# IR_Transceiver.net
KiCad netlist of a schematic drawn in EAGLE
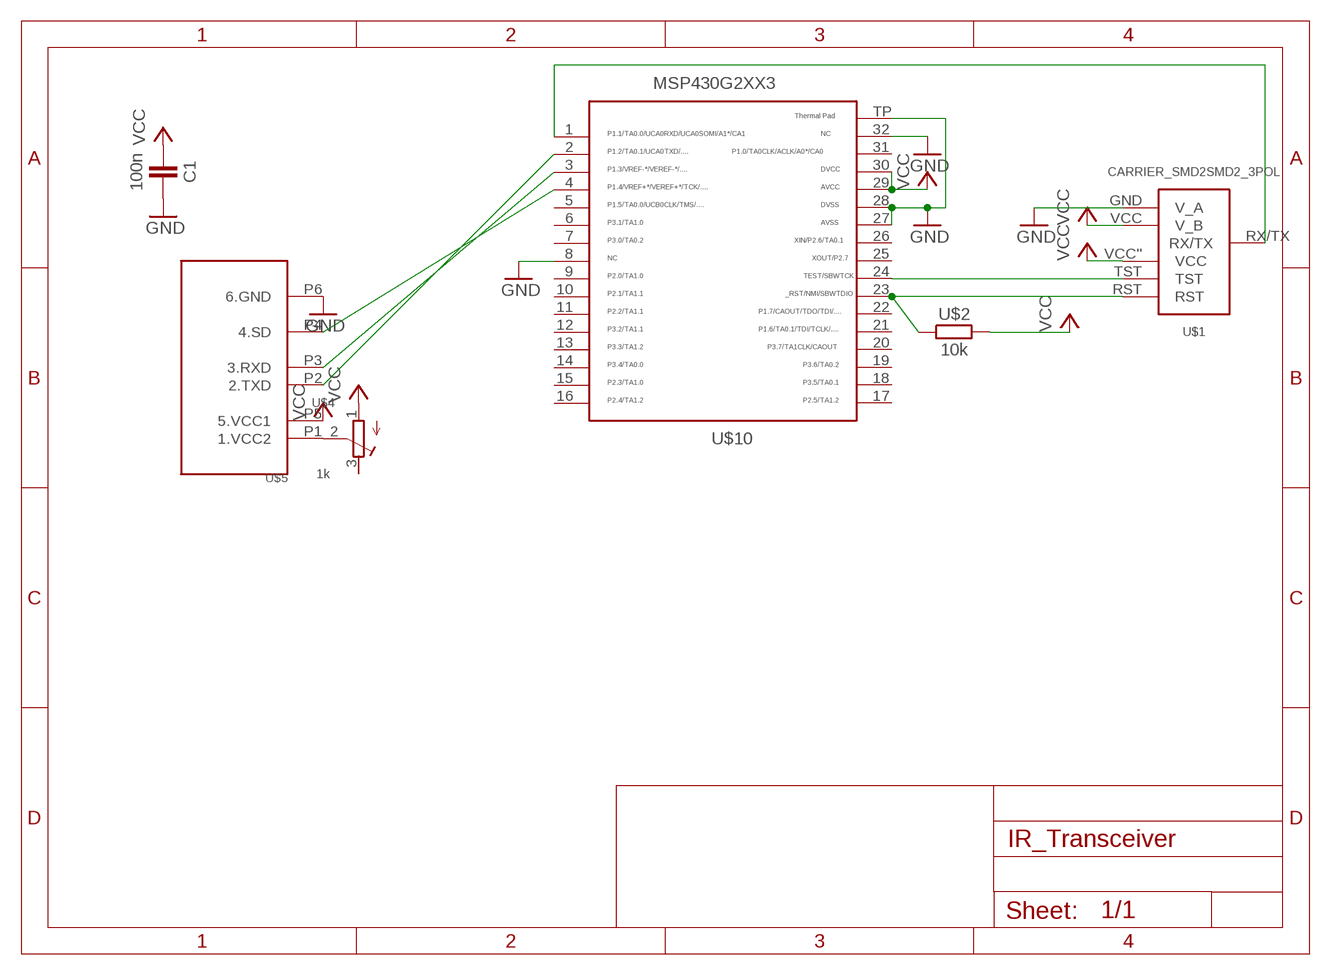
[diagram p0: schematic, sheet 1]

(export (version "E")
  (design (tool "Eeschema 10.0.6"))
  (components
    (comp (ref "C1")
      (value "100n")
      (footprint "eagle-import:603")
      (libsource (lib "eagle-import") (part "CAPACITOR"))
    )
    (comp (ref "U$1")
      (value "CARRIER_SMD2SMD2_3POL")
      (footprint "eagle-import:CARRIER_SMD2_3POL")
      (libsource (lib "eagle-import") (part "CARRIER_SMD2SMD2_3POL"))
    )
    (comp (ref "U$2")
      (value "10k")
      (footprint "eagle-import:603")
      (libsource (lib "eagle-import") (part "RESISTOR0603"))
    )
    (comp (ref "U$4")
      (value "1k")
      (footprint "eagle-import:POTI35")
      (libsource (lib "eagle-import") (part "POTISMD"))
    )
    (comp (ref "U$5")
      (value "TFBS4711")
      (footprint "eagle-import:TFBS4711")
      (libsource (lib "eagle-import") (part "TFBS4711"))
    )
    (comp (ref "U$10")
      (value "MSP430G2553")
      (footprint "eagle-import:QFN32")
      (libsource (lib "eagle-import") (part "MSP430G2553"))
    )
  )
  (nets
    (net (code "1") (name "GND") (class "Default")
      (node (ref "C1") (pin "2") (pinfunction "2_2") (pintype "passive"))
      (node (ref "U$1") (pin "GND") (pinfunction "V_A_GND") (pintype "bidirectional"))
      (node (ref "U$10") (pin "27") (pinfunction "27_27") (pintype "bidirectional"))
      (node (ref "U$10") (pin "28") (pinfunction "28_28") (pintype "bidirectional"))
      (node (ref "U$10") (pin "32") (pinfunction "32_32") (pintype "bidirectional"))
      (node (ref "U$10") (pin "8") (pinfunction "8_8") (pintype "bidirectional"))
      (node (ref "U$10") (pin "TP") (pinfunction "TP_TP") (pintype "bidirectional"))
      (node (ref "U$5") (pin "P6") (pinfunction "6.GND_P6") (pintype "bidirectional"))
    )
    (net (code "2") (name "Net-(U$1-PadRST)") (class "Default")
      (node (ref "U$1") (pin "RST") (pinfunction "RST_RST") (pintype "bidirectional"))
      (node (ref "U$10") (pin "23") (pinfunction "23_23") (pintype "bidirectional"))
      (node (ref "U$2") (pin "1") (pinfunction "1_1") (pintype "passive"))
    )
    (net (code "3") (name "Net-(U$1-PadRX{slash}TX)") (class "Default")
      (node (ref "U$1") (pin "RX/TX") (pinfunction "RX/TX_RX/TX") (pintype "bidirectional"))
      (node (ref "U$10") (pin "1") (pinfunction "1_1") (pintype "bidirectional"))
    )
    (net (code "4") (name "Net-(U$1-PadTST)") (class "Default")
      (node (ref "U$1") (pin "TST") (pinfunction "TST_TST") (pintype "bidirectional"))
      (node (ref "U$10") (pin "24") (pinfunction "24_24") (pintype "bidirectional"))
    )
    (net (code "5") (name "Net-(U$4-S)") (class "Default")
      (node (ref "U$4") (pin "2") (pinfunction "S_2") (pintype "passive"))
      (node (ref "U$5") (pin "P1") (pinfunction "1.VCC2_P1") (pintype "bidirectional"))
    )
    (net (code "6") (name "Net-(U$5-2.TXD)") (class "Default")
      (node (ref "U$10") (pin "2") (pinfunction "2_2") (pintype "bidirectional"))
      (node (ref "U$5") (pin "P2") (pinfunction "2.TXD_P2") (pintype "bidirectional"))
    )
    (net (code "7") (name "Net-(U$5-3.RXD)") (class "Default")
      (node (ref "U$10") (pin "3") (pinfunction "3_3") (pintype "bidirectional"))
      (node (ref "U$5") (pin "P3") (pinfunction "3.RXD_P3") (pintype "bidirectional"))
    )
    (net (code "8") (name "Net-(U$5-4.SD)") (class "Default")
      (node (ref "U$10") (pin "4") (pinfunction "4_4") (pintype "bidirectional"))
      (node (ref "U$5") (pin "P4") (pinfunction "4.SD_P4") (pintype "bidirectional"))
    )
    (net (code "9") (name "VCC") (class "Default")
      (node (ref "C1") (pin "1") (pinfunction "1_1") (pintype "passive"))
      (node (ref "U$1") (pin "VCC") (pinfunction "V_B_VCC") (pintype "bidirectional"))
      (node (ref "U$1") (pin "VCC''") (pinfunction "VCC_VCC''") (pintype "bidirectional"))
      (node (ref "U$10") (pin "29") (pinfunction "29_29") (pintype "bidirectional"))
      (node (ref "U$10") (pin "30") (pinfunction "30_30") (pintype "bidirectional"))
      (node (ref "U$2") (pin "2") (pinfunction "2_2") (pintype "passive"))
      (node (ref "U$4") (pin "1") (pinfunction "A_1") (pintype "passive"))
      (node (ref "U$5") (pin "P5") (pinfunction "5.VCC1_P5") (pintype "bidirectional"))
    )
    (net (code "10") (name "unconnected-(U$4-E-Pad3)") (class "Default")
      (node (ref "U$4") (pin "3") (pinfunction "E_3") (pintype "passive"))
    )
    (net (code "11") (name "unconnected-(U$10-Pad5)") (class "Default")
      (node (ref "U$10") (pin "5") (pinfunction "5_5") (pintype "bidirectional"))
    )
    (net (code "12") (name "unconnected-(U$10-Pad6)") (class "Default")
      (node (ref "U$10") (pin "6") (pinfunction "6_6") (pintype "bidirectional"))
    )
    (net (code "13") (name "unconnected-(U$10-Pad7)") (class "Default")
      (node (ref "U$10") (pin "7") (pinfunction "7_7") (pintype "bidirectional"))
    )
    (net (code "14") (name "unconnected-(U$10-Pad9)") (class "Default")
      (node (ref "U$10") (pin "9") (pinfunction "9_9") (pintype "bidirectional"))
    )
    (net (code "15") (name "unconnected-(U$10-Pad10)") (class "Default")
      (node (ref "U$10") (pin "10") (pinfunction "10_10") (pintype "bidirectional"))
    )
    (net (code "16") (name "unconnected-(U$10-Pad11)") (class "Default")
      (node (ref "U$10") (pin "11") (pinfunction "11_11") (pintype "bidirectional"))
    )
    (net (code "17") (name "unconnected-(U$10-Pad12)") (class "Default")
      (node (ref "U$10") (pin "12") (pinfunction "12_12") (pintype "bidirectional"))
    )
    (net (code "18") (name "unconnected-(U$10-Pad13)") (class "Default")
      (node (ref "U$10") (pin "13") (pinfunction "13_13") (pintype "bidirectional"))
    )
    (net (code "19") (name "unconnected-(U$10-Pad14)") (class "Default")
      (node (ref "U$10") (pin "14") (pinfunction "14_14") (pintype "bidirectional"))
    )
    (net (code "20") (name "unconnected-(U$10-Pad15)") (class "Default")
      (node (ref "U$10") (pin "15") (pinfunction "15_15") (pintype "bidirectional"))
    )
    (net (code "21") (name "unconnected-(U$10-Pad16)") (class "Default")
      (node (ref "U$10") (pin "16") (pinfunction "16_16") (pintype "bidirectional"))
    )
    (net (code "22") (name "unconnected-(U$10-Pad17)") (class "Default")
      (node (ref "U$10") (pin "17") (pinfunction "17_17") (pintype "bidirectional"))
    )
    (net (code "23") (name "unconnected-(U$10-Pad18)") (class "Default")
      (node (ref "U$10") (pin "18") (pinfunction "18_18") (pintype "bidirectional"))
    )
    (net (code "24") (name "unconnected-(U$10-Pad19)") (class "Default")
      (node (ref "U$10") (pin "19") (pinfunction "19_19") (pintype "bidirectional"))
    )
    (net (code "25") (name "unconnected-(U$10-Pad20)") (class "Default")
      (node (ref "U$10") (pin "20") (pinfunction "20_20") (pintype "bidirectional"))
    )
    (net (code "26") (name "unconnected-(U$10-Pad21)") (class "Default")
      (node (ref "U$10") (pin "21") (pinfunction "21_21") (pintype "bidirectional"))
    )
    (net (code "27") (name "unconnected-(U$10-Pad22)") (class "Default")
      (node (ref "U$10") (pin "22") (pinfunction "22_22") (pintype "bidirectional"))
    )
    (net (code "28") (name "unconnected-(U$10-Pad25)") (class "Default")
      (node (ref "U$10") (pin "25") (pinfunction "25_25") (pintype "bidirectional"))
    )
    (net (code "29") (name "unconnected-(U$10-Pad26)") (class "Default")
      (node (ref "U$10") (pin "26") (pinfunction "26_26") (pintype "bidirectional"))
    )
    (net (code "30") (name "unconnected-(U$10-Pad31)") (class "Default")
      (node (ref "U$10") (pin "31") (pinfunction "31_31") (pintype "bidirectional"))
    )
  )
)
